# Quad-Stage-Prototype_Driver_V1_0.net
KiCad netlist of a schematic drawn in Altium Designer
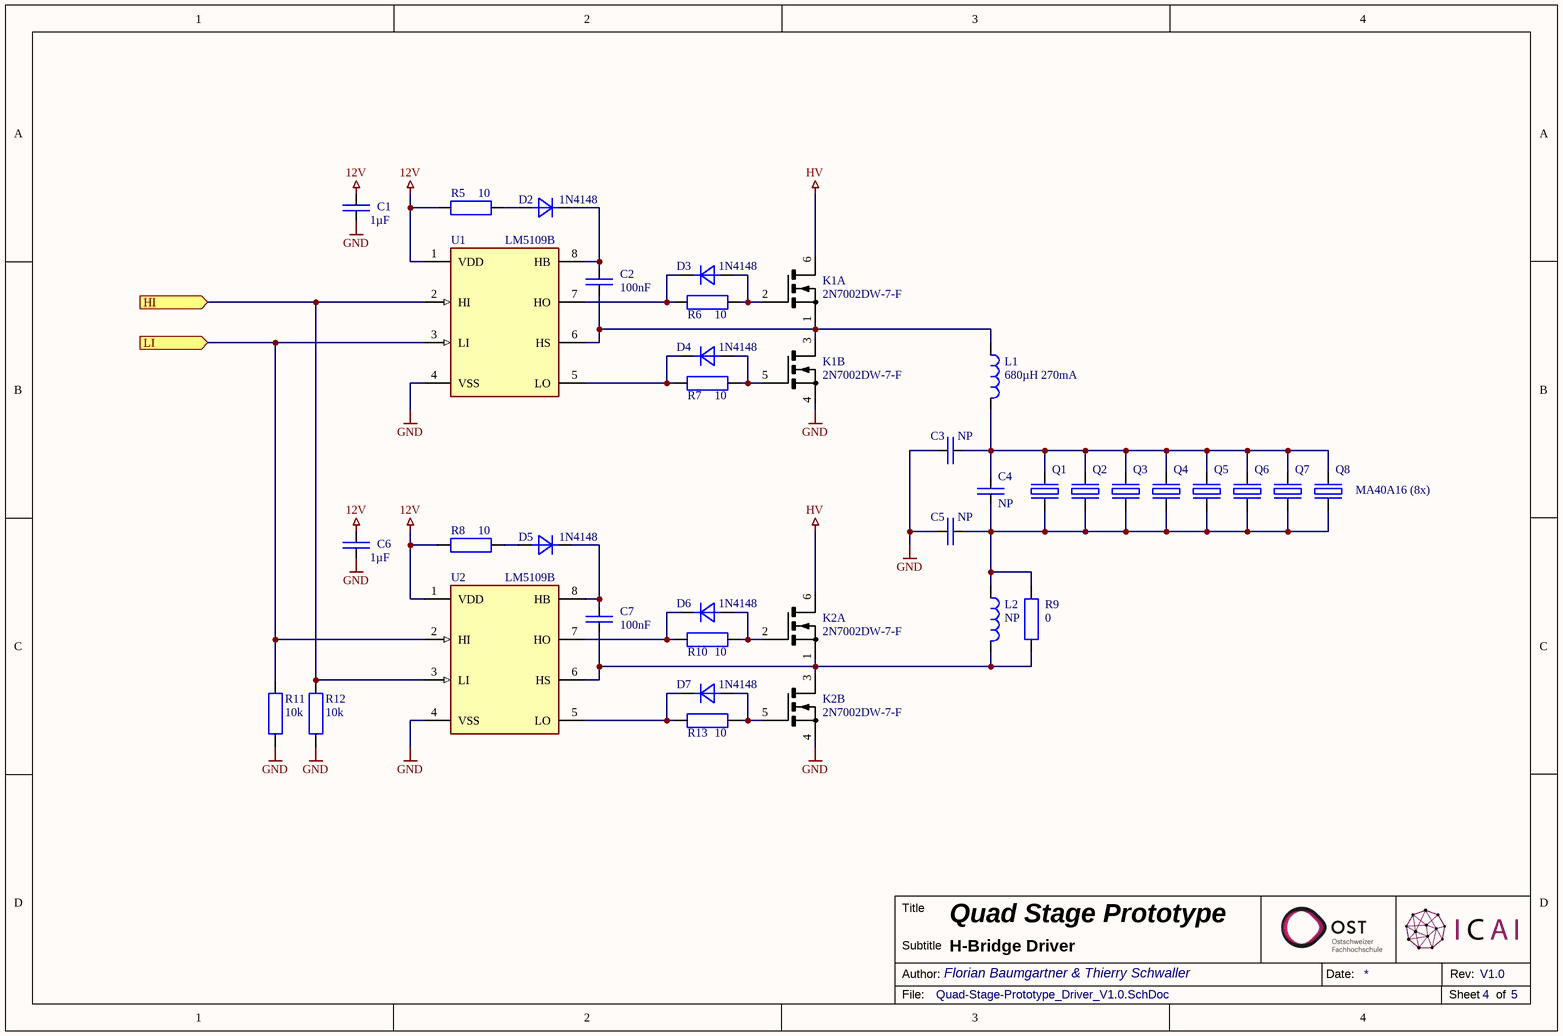
[diagram p0: Quad-Stage-Prototype_Driver_V1.0.SchDoc]

(export (version "E")
  (design (tool "Eeschema 10.0.6"))
  (components
    (comp (ref "C1")
      (value "1µF")
      (footprint "SMD Keramikkondensator 0603")
      (description "CAP-MK")
      (libsource (lib "AudioAmp") (part "C-CAPACITOR"))
    )
    (comp (ref "C2")
      (value "100nF")
      (footprint "SMD Keramikkondensator 0603")
      (description "CAP-MK")
      (libsource (lib "AudioAmp") (part "C-CAPACITOR"))
    )
    (comp (ref "C3")
      (value "NP")
      (footprint "SMD Keramikkondensator 0603")
      (description "CAP-MK")
      (libsource (lib "AudioAmp") (part "C-CAPACITOR"))
    )
    (comp (ref "C4")
      (value "NP")
      (footprint "SMD Keramikkondensator 0603")
      (description "CAP-MK")
      (libsource (lib "AudioAmp") (part "C-CAPACITOR"))
    )
    (comp (ref "C5")
      (value "NP")
      (footprint "SMD Keramikkondensator 0603")
      (description "CAP-MK")
      (libsource (lib "AudioAmp") (part "C-CAPACITOR"))
    )
    (comp (ref "C6")
      (value "1µF")
      (footprint "SMD Keramikkondensator 0603")
      (description "CAP-MK")
      (libsource (lib "AudioAmp") (part "C-CAPACITOR"))
    )
    (comp (ref "C7")
      (value "100nF")
      (footprint "SMD Keramikkondensator 0603")
      (description "CAP-MK")
      (libsource (lib "AudioAmp") (part "C-CAPACITOR"))
    )
    (comp (ref "D2")
      (value "1N4148")
      (footprint "SMD Diode SOD-123")
      (description "DIODE (alt V)")
      (libsource (lib "TFS Integrated Library") (part "R-DIODE"))
    )
    (comp (ref "D3")
      (value "1N4148")
      (footprint "SMD Diode SOD-123")
      (description "DIODE (alt V)")
      (libsource (lib "TFS Integrated Library") (part "R-DIODE"))
    )
    (comp (ref "D4")
      (value "1N4148")
      (footprint "SMD Diode SOD-123")
      (description "DIODE (alt V)")
      (libsource (lib "TFS Integrated Library") (part "R-DIODE"))
    )
    (comp (ref "D5")
      (value "1N4148")
      (footprint "SMD Diode SOD-123")
      (description "DIODE (alt V)")
      (libsource (lib "TFS Integrated Library") (part "R-DIODE"))
    )
    (comp (ref "D6")
      (value "1N4148")
      (footprint "SMD Diode SOD-123")
      (description "DIODE (alt V)")
      (libsource (lib "TFS Integrated Library") (part "R-DIODE"))
    )
    (comp (ref "D7")
      (value "1N4148")
      (footprint "SMD Diode SOD-123")
      (description "DIODE (alt V)")
      (libsource (lib "TFS Integrated Library") (part "R-DIODE"))
    )
    (comp (ref "K1")
      (value "2N7002DW-7-F")
      (footprint "SMD IC SOT-363 (SC-70-6)")
      (description "Dual N-Channel MOSFET")
      (libsource (lib "Quad-Stage-Prototype") (part "K-2N7002DW-7-F"))
    )
    (comp (ref "K2")
      (value "2N7002DW-7-F")
      (footprint "SMD IC SOT-363 (SC-70-6)")
      (description "Dual N-Channel MOSFET")
      (libsource (lib "Quad-Stage-Prototype") (part "K-2N7002DW-7-F"))
    )
    (comp (ref "L1")
      (value "680µH 270mA")
      (footprint "SMD Inductor 7x7x4.5")
      (description "Shielded Power Inductor")
      (libsource (lib "") (part "L-COIL_1"))
    )
    (comp (ref "L2")
      (value "NP")
      (footprint "SMD Inductor 7x7x4.5 NP")
      (description "Shielded Power Inductor")
      (libsource (lib "Nixie-Test") (part "L-COIL"))
    )
    (comp (ref "Q1")
      (value "MA40A16")
      (footprint "THT Transducer (MA40A16)")
      (description "Ultrasonic Transducer")
      (libsource (lib "Quad-Stage-Prototype") (part "Q-Piezo"))
    )
    (comp (ref "Q2")
      (value "MA40A16")
      (footprint "THT Transducer (MA40A16)")
      (description "Ultrasonic Transducer")
      (libsource (lib "Quad-Stage-Prototype") (part "Q-Piezo"))
    )
    (comp (ref "Q3")
      (value "MA40A16")
      (footprint "THT Transducer (MA40A16)")
      (description "Ultrasonic Transducer")
      (libsource (lib "Quad-Stage-Prototype") (part "Q-Piezo"))
    )
    (comp (ref "Q4")
      (value "MA40A16")
      (footprint "THT Transducer (MA40A16)")
      (description "Ultrasonic Transducer")
      (libsource (lib "Quad-Stage-Prototype") (part "Q-Piezo"))
    )
    (comp (ref "Q5")
      (value "MA40A16")
      (footprint "THT Transducer (MA40A16)")
      (description "Ultrasonic Transducer")
      (libsource (lib "Quad-Stage-Prototype") (part "Q-Piezo"))
    )
    (comp (ref "Q6")
      (value "MA40A16")
      (footprint "THT Transducer (MA40A16)")
      (description "Ultrasonic Transducer")
      (libsource (lib "Quad-Stage-Prototype") (part "Q-Piezo"))
    )
    (comp (ref "Q7")
      (value "MA40A16")
      (footprint "THT Transducer (MA40A16)")
      (description "Ultrasonic Transducer")
      (libsource (lib "Quad-Stage-Prototype") (part "Q-Piezo"))
    )
    (comp (ref "Q8")
      (value "MA40A16")
      (footprint "THT Transducer (MA40A16)")
      (description "Ultrasonic Transducer")
      (libsource (lib "Quad-Stage-Prototype") (part "Q-Piezo"))
    )
    (comp (ref "R5")
      (value "10")
      (footprint "SMD Widerstand 0603")
      (description "RES (E=Heizwiderstand B=Messwandler)")
      (libsource (lib "TFS Integrated Library") (part "R-RESISTOR"))
    )
    (comp (ref "R6")
      (value "10")
      (footprint "SMD Widerstand 0603")
      (description "RES (E=Heizwiderstand B=Messwandler)")
      (libsource (lib "TFS Integrated Library") (part "R-RESISTOR"))
    )
    (comp (ref "R7")
      (value "10")
      (footprint "SMD Widerstand 0603")
      (description "RES (E=Heizwiderstand B=Messwandler)")
      (libsource (lib "TFS Integrated Library") (part "R-RESISTOR"))
    )
    (comp (ref "R8")
      (value "10")
      (footprint "SMD Widerstand 0603")
      (description "RES (E=Heizwiderstand B=Messwandler)")
      (libsource (lib "TFS Integrated Library") (part "R-RESISTOR"))
    )
    (comp (ref "R9")
      (value "0")
      (footprint "SMD Widerstand 0603")
      (description "RES (E=Heizwiderstand B=Messwandler)")
      (libsource (lib "") (part "R-RESISTOR_1"))
    )
    (comp (ref "R10")
      (value "10")
      (footprint "SMD Widerstand 0603")
      (description "RES (E=Heizwiderstand B=Messwandler)")
      (libsource (lib "TFS Integrated Library") (part "R-RESISTOR"))
    )
    (comp (ref "R11")
      (value "10k")
      (footprint "SMD Widerstand 0603")
      (description "RES (E=Heizwiderstand B=Messwandler)")
      (libsource (lib "") (part "R-RESISTOR_1"))
    )
    (comp (ref "R12")
      (value "10k")
      (footprint "SMD Widerstand 0603")
      (description "RES (E=Heizwiderstand B=Messwandler)")
      (libsource (lib "") (part "R-RESISTOR_1"))
    )
    (comp (ref "R13")
      (value "10")
      (footprint "SMD Widerstand 0603")
      (description "RES (E=Heizwiderstand B=Messwandler)")
      (libsource (lib "TFS Integrated Library") (part "R-RESISTOR"))
    )
    (comp (ref "U1")
      (value "LM5109B")
      (footprint "SMD IC SOIC-8")
      (description "High Voltage 1A Peak Half Bridge Gate Driver")
      (libsource (lib "Quad-Stage-Prototype") (part "U-LM5109B"))
    )
    (comp (ref "U2")
      (value "LM5109B")
      (footprint "SMD IC SOIC-8")
      (description "High Voltage 1A Peak Half Bridge Gate Driver")
      (libsource (lib "Quad-Stage-Prototype") (part "U-LM5109B"))
    )
  )
  (nets
    (net (code "1") (name "/HI") (class "Default")
      (node (ref "R12") (pin "2") (pinfunction "2_2") (pintype "passive"))
      (node (ref "U1") (pin "2") (pinfunction "HI_2") (pintype "input"))
      (node (ref "U2") (pin "3") (pinfunction "LI_3") (pintype "input"))
    )
    (net (code "2") (name "/LI") (class "Default")
      (node (ref "R11") (pin "2") (pinfunction "2_2") (pintype "passive"))
      (node (ref "U1") (pin "3") (pinfunction "LI_3") (pintype "input"))
      (node (ref "U2") (pin "2") (pinfunction "HI_2") (pintype "input"))
    )
    (net (code "3") (name "12V") (class "Default")
      (node (ref "C1") (pin "2") (pinfunction "2_2") (pintype "passive"))
      (node (ref "C6") (pin "2") (pinfunction "2_2") (pintype "passive"))
      (node (ref "R5") (pin "2") (pinfunction "2_2") (pintype "passive"))
      (node (ref "R8") (pin "2") (pinfunction "2_2") (pintype "passive"))
      (node (ref "U1") (pin "1") (pinfunction "VDD_1") (pintype "power_in"))
      (node (ref "U2") (pin "1") (pinfunction "VDD_1") (pintype "power_in"))
    )
    (net (code "4") (name "GND") (class "Default")
      (node (ref "C1") (pin "1") (pinfunction "1_1") (pintype "passive"))
      (node (ref "C3") (pin "2") (pinfunction "2_2") (pintype "passive"))
      (node (ref "C5") (pin "2") (pinfunction "2_2") (pintype "passive"))
      (node (ref "C6") (pin "1") (pinfunction "1_1") (pintype "passive"))
      (node (ref "K1") (pin "4") (pinfunction "S2_4") (pintype "passive"))
      (node (ref "K2") (pin "4") (pinfunction "S2_4") (pintype "passive"))
      (node (ref "R11") (pin "1") (pinfunction "1_1") (pintype "passive"))
      (node (ref "R12") (pin "1") (pinfunction "1_1") (pintype "passive"))
      (node (ref "U1") (pin "4") (pinfunction "VSS_4") (pintype "power_in"))
      (node (ref "U2") (pin "4") (pinfunction "VSS_4") (pintype "power_in"))
    )
    (net (code "5") (name "HV") (class "Default")
      (node (ref "K1") (pin "6") (pinfunction "D1_6") (pintype "passive"))
      (node (ref "K2") (pin "6") (pinfunction "D1_6") (pintype "passive"))
    )
    (net (code "6") (name "Net-(C3-Pad1)") (class "Default")
      (node (ref "C3") (pin "1") (pinfunction "1_1") (pintype "passive"))
      (node (ref "C4") (pin "2") (pinfunction "2_2") (pintype "passive"))
      (node (ref "L1") (pin "2") (pinfunction "2_2") (pintype "passive"))
      (node (ref "Q1") (pin "2") (pinfunction "2_2") (pintype "passive"))
      (node (ref "Q2") (pin "2") (pinfunction "2_2") (pintype "passive"))
      (node (ref "Q3") (pin "2") (pinfunction "2_2") (pintype "passive"))
      (node (ref "Q4") (pin "2") (pinfunction "2_2") (pintype "passive"))
      (node (ref "Q5") (pin "2") (pinfunction "2_2") (pintype "passive"))
      (node (ref "Q6") (pin "2") (pinfunction "2_2") (pintype "passive"))
      (node (ref "Q7") (pin "2") (pinfunction "2_2") (pintype "passive"))
      (node (ref "Q8") (pin "2") (pinfunction "2_2") (pintype "passive"))
    )
    (net (code "7") (name "Net-(C4-Pad1)") (class "Default")
      (node (ref "C4") (pin "1") (pinfunction "1_1") (pintype "passive"))
      (node (ref "C5") (pin "1") (pinfunction "1_1") (pintype "passive"))
      (node (ref "L2") (pin "2") (pinfunction "2_2") (pintype "passive"))
      (node (ref "Q1") (pin "1") (pinfunction "1_1") (pintype "passive"))
      (node (ref "Q2") (pin "1") (pinfunction "1_1") (pintype "passive"))
      (node (ref "Q3") (pin "1") (pinfunction "1_1") (pintype "passive"))
      (node (ref "Q4") (pin "1") (pinfunction "1_1") (pintype "passive"))
      (node (ref "Q5") (pin "1") (pinfunction "1_1") (pintype "passive"))
      (node (ref "Q6") (pin "1") (pinfunction "1_1") (pintype "passive"))
      (node (ref "Q7") (pin "1") (pinfunction "1_1") (pintype "passive"))
      (node (ref "Q8") (pin "1") (pinfunction "1_1") (pintype "passive"))
      (node (ref "R9") (pin "2") (pinfunction "2_2") (pintype "passive"))
    )
    (net (code "8") (name "Net-(D2-PadA)") (class "Default")
      (node (ref "D2") (pin "A") (pinfunction "A_A") (pintype "passive"))
      (node (ref "R5") (pin "1") (pinfunction "1_1") (pintype "passive"))
    )
    (net (code "9") (name "Net-(D5-PadA)") (class "Default")
      (node (ref "D5") (pin "A") (pinfunction "A_A") (pintype "passive"))
      (node (ref "R8") (pin "1") (pinfunction "1_1") (pintype "passive"))
    )
    (net (code "10") (name "Net-(K1A-G1)") (class "Default")
      (node (ref "D3") (pin "A") (pinfunction "A_A") (pintype "passive"))
      (node (ref "K1") (pin "2") (pinfunction "G1_2") (pintype "passive"))
      (node (ref "R6") (pin "1") (pinfunction "1_1") (pintype "passive"))
    )
    (net (code "11") (name "Net-(K1A-S1)") (class "Default")
      (node (ref "C2") (pin "1") (pinfunction "1_1") (pintype "passive"))
      (node (ref "K1") (pin "1") (pinfunction "S1_1") (pintype "passive"))
      (node (ref "K1") (pin "3") (pinfunction "D2_3") (pintype "passive"))
      (node (ref "L1") (pin "1") (pinfunction "1_1") (pintype "passive"))
      (node (ref "U1") (pin "6") (pinfunction "HS_6") (pintype "passive"))
    )
    (net (code "12") (name "Net-(K1B-G2)") (class "Default")
      (node (ref "D4") (pin "A") (pinfunction "A_A") (pintype "passive"))
      (node (ref "K1") (pin "5") (pinfunction "G2_5") (pintype "passive"))
      (node (ref "R7") (pin "1") (pinfunction "1_1") (pintype "passive"))
    )
    (net (code "13") (name "Net-(K2A-G1)") (class "Default")
      (node (ref "D6") (pin "A") (pinfunction "A_A") (pintype "passive"))
      (node (ref "K2") (pin "2") (pinfunction "G1_2") (pintype "passive"))
      (node (ref "R10") (pin "1") (pinfunction "1_1") (pintype "passive"))
    )
    (net (code "14") (name "Net-(K2A-S1)") (class "Default")
      (node (ref "C7") (pin "1") (pinfunction "1_1") (pintype "passive"))
      (node (ref "K2") (pin "1") (pinfunction "S1_1") (pintype "passive"))
      (node (ref "K2") (pin "3") (pinfunction "D2_3") (pintype "passive"))
      (node (ref "L2") (pin "1") (pinfunction "1_1") (pintype "passive"))
      (node (ref "R9") (pin "1") (pinfunction "1_1") (pintype "passive"))
      (node (ref "U2") (pin "6") (pinfunction "HS_6") (pintype "passive"))
    )
    (net (code "15") (name "Net-(K2B-G2)") (class "Default")
      (node (ref "D7") (pin "A") (pinfunction "A_A") (pintype "passive"))
      (node (ref "K2") (pin "5") (pinfunction "G2_5") (pintype "passive"))
      (node (ref "R13") (pin "1") (pinfunction "1_1") (pintype "passive"))
    )
    (net (code "16") (name "Net-(U1-HB)") (class "Default")
      (node (ref "C2") (pin "2") (pinfunction "2_2") (pintype "passive"))
      (node (ref "D2") (pin "K") (pinfunction "K_K") (pintype "passive"))
      (node (ref "U1") (pin "8") (pinfunction "HB_8") (pintype "passive"))
    )
    (net (code "17") (name "Net-(U1-HO)") (class "Default")
      (node (ref "D3") (pin "K") (pinfunction "K_K") (pintype "passive"))
      (node (ref "R6") (pin "2") (pinfunction "2_2") (pintype "passive"))
      (node (ref "U1") (pin "7") (pinfunction "HO_7") (pintype "passive"))
    )
    (net (code "18") (name "Net-(U1-LO)") (class "Default")
      (node (ref "D4") (pin "K") (pinfunction "K_K") (pintype "passive"))
      (node (ref "R7") (pin "2") (pinfunction "2_2") (pintype "passive"))
      (node (ref "U1") (pin "5") (pinfunction "LO_5") (pintype "passive"))
    )
    (net (code "19") (name "Net-(U2-HB)") (class "Default")
      (node (ref "C7") (pin "2") (pinfunction "2_2") (pintype "passive"))
      (node (ref "D5") (pin "K") (pinfunction "K_K") (pintype "passive"))
      (node (ref "U2") (pin "8") (pinfunction "HB_8") (pintype "passive"))
    )
    (net (code "20") (name "Net-(U2-HO)") (class "Default")
      (node (ref "D6") (pin "K") (pinfunction "K_K") (pintype "passive"))
      (node (ref "R10") (pin "2") (pinfunction "2_2") (pintype "passive"))
      (node (ref "U2") (pin "7") (pinfunction "HO_7") (pintype "passive"))
    )
    (net (code "21") (name "Net-(U2-LO)") (class "Default")
      (node (ref "D7") (pin "K") (pinfunction "K_K") (pintype "passive"))
      (node (ref "R13") (pin "2") (pinfunction "2_2") (pintype "passive"))
      (node (ref "U2") (pin "5") (pinfunction "LO_5") (pintype "passive"))
    )
  )
)
